# Rectifier_shutdown_LT1910.net
KiCad netlist of a schematic drawn in Altium Designer
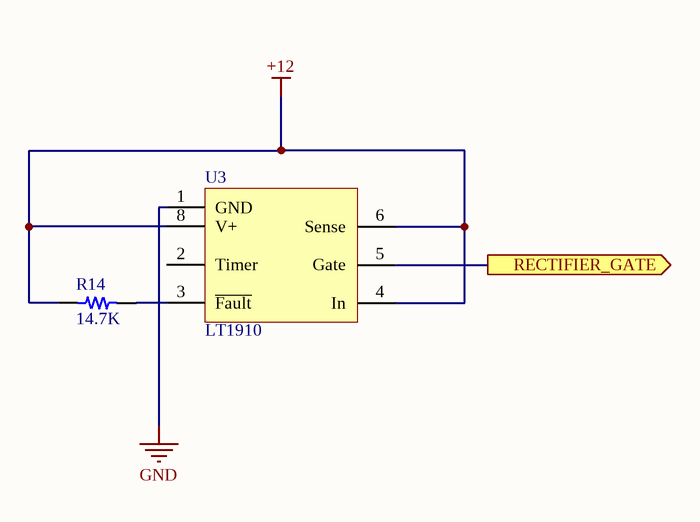
[diagram p0: Rectifier_shutdown_LT1910.SchDoc]

(export (version "E")
  (design (tool "Eeschema 10.0.6"))
  (components
    (comp (ref "R14")
      (value "14.7K")
      (footprint "RES 0805/2012")
      (fields (field (name "TOLERANCE") "0.5%") (field (name "POWER") "1/10W"))
      (libsource (lib "Altium-Lib") (part "Resistor"))
    )
    (comp (ref "U3")
      (value "LT1910")
      (footprint "SOIC-8")
      (description "Protected High Side MOSFET Driver")
      (libsource (lib "Altium-Lib") (part "LT1910"))
    )
  )
  (nets
    (net (code "1") (name "+12") (class "Default")
      (node (ref "R14") (pin "1") (pinfunction "1_1") (pintype "passive"))
      (node (ref "U3") (pin "4") (pinfunction "In_4") (pintype "passive"))
      (node (ref "U3") (pin "6") (pinfunction "Sense_6") (pintype "power_in"))
      (node (ref "U3") (pin "8") (pinfunction "V+_8") (pintype "power_in"))
    )
    (net (code "2") (name "/RECTIFIER_GATE") (class "Default")
      (node (ref "U3") (pin "5") (pinfunction "Gate_5") (pintype "power_in"))
    )
    (net (code "3") (name "GND") (class "Default")
      (node (ref "U3") (pin "1") (pinfunction "GND_1") (pintype "power_in"))
    )
    (net (code "4") (name "Net-(U3-Fault)") (class "Default")
      (node (ref "R14") (pin "2") (pinfunction "2_2") (pintype "passive"))
      (node (ref "U3") (pin "3") (pinfunction "Fault_3") (pintype "passive"))
    )
    (net (code "5") (name "unconnected-(U3-Timer-Pad2)") (class "Default")
      (node (ref "U3") (pin "2") (pinfunction "Timer_2") (pintype "passive"))
    )
  )
)
